# RC_Remote_SCH.net
KiCad netlist of a schematic drawn in Altium Designer
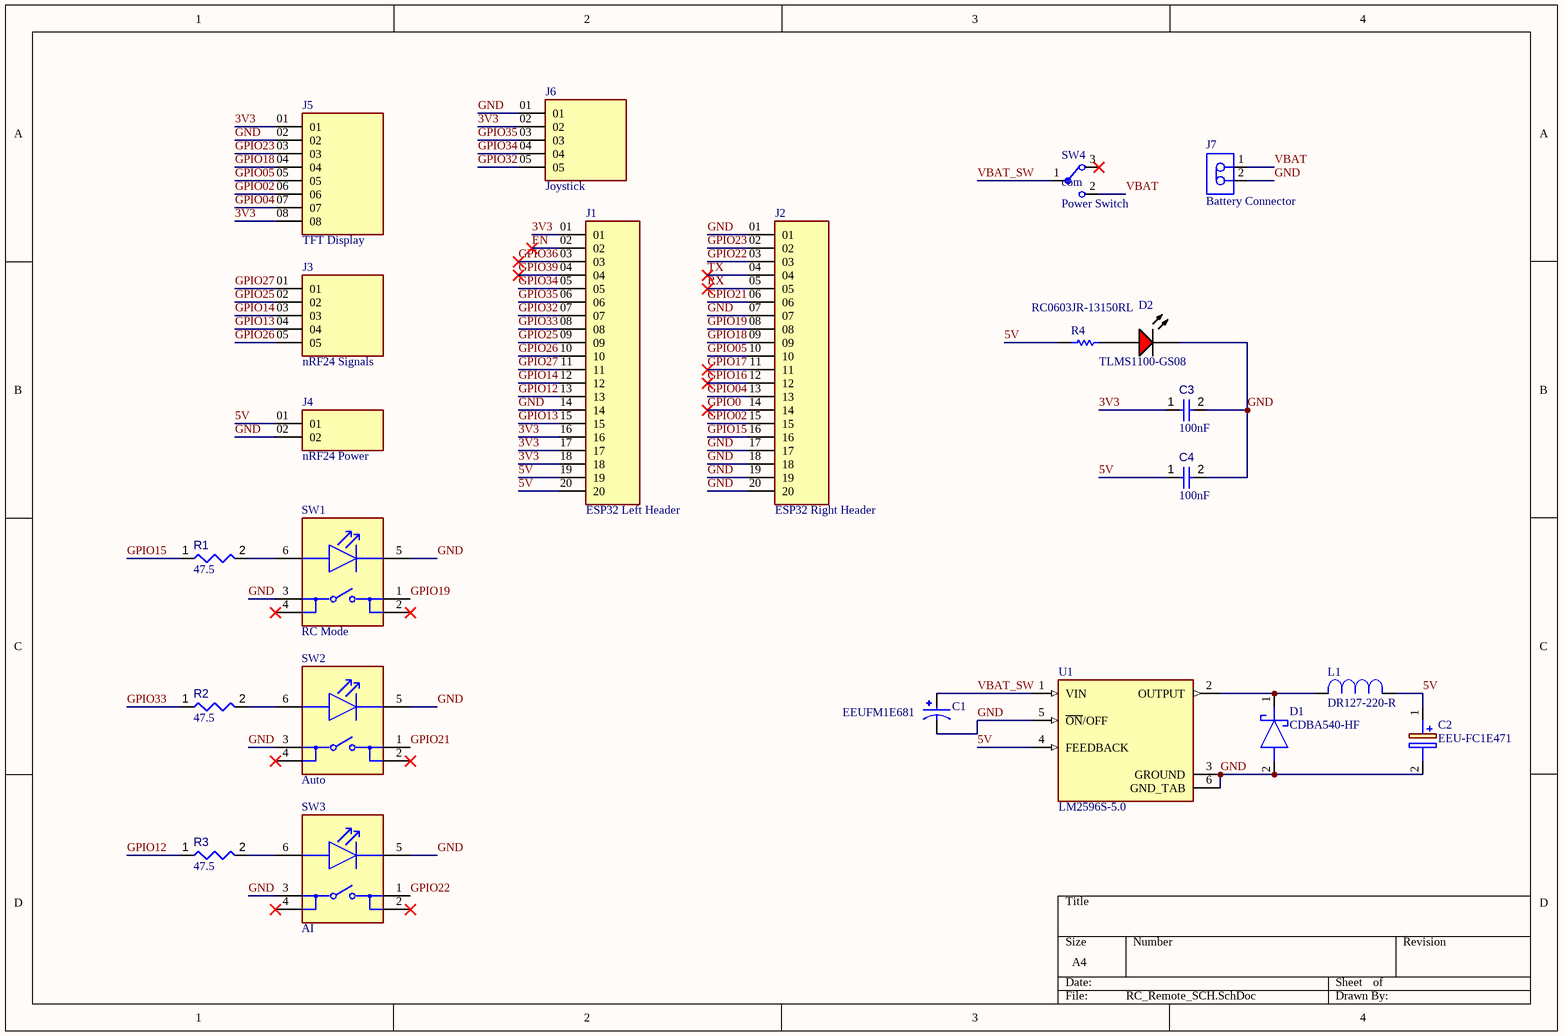
[diagram p0: RC_Remote_SCH.SchDoc]

(export (version "E")
  (design (tool "Eeschema 10.0.6"))
  (components
    (comp (ref "C1")
      (value "EEUFM1E681")
      (footprint "CAPPRD500W60D1000H2000")
      (description "680F 25V Aluminum Electrolytic Capacitors Radial, Can 5000 Hrs @ 105C")
      (fields (field (name "MF") "Panasonic") (field (name "DIGI-KEY_PART_NUMBER") "P12390-ND"))
      (libsource (lib "EEUFM1E681") (part "EEUFM1E681"))
    )
    (comp (ref "C2")
      (value "EEU-FC1E471")
      (footprint "SamacSys:CAPPRD350W65D815H2200")
      (description "Capacitor Polarised")
      (fields (field (name "MOUSER PART NUMBER") "667-EEU-FC1E471"))
      (libsource (lib "*") (part "EEU-FC1E471"))
    )
    (comp (ref "C3")
      (value "100nF")
      (footprint "CAPC1608X90X40NL10T20")
      (description "Chip Capacitor, 100 nF, +/- 10%, 50 V, 0603 (1608 Metric)")
      (fields (field (name "TOLERANCE") "10%") (field (name "Comment") "Capacitor 100 nF +/-10% 50 V 0603"))
      (libsource (lib "Shubh Patel") (part "CAP-NP-2"))
    )
    (comp (ref "C4")
      (value "100nF")
      (footprint "CAPC1608X90X40NL10T20")
      (description "Chip Capacitor, 100 nF, +/- 10%, 50 V, 0603 (1608 Metric)")
      (fields (field (name "TOLERANCE") "10%") (field (name "Comment") "Capacitor 100 nF +/-10% 50 V 0603"))
      (libsource (lib "Shubh Patel") (part "CAP-NP-2"))
    )
    (comp (ref "D1")
      (value "CDBA540-HF")
      (footprint "SamacSys:DIOM5225X250N")
      (description "Schottky Diode")
      (fields (field (name "MOUSER PART NUMBER") "750-CDBA540-HF"))
      (libsource (lib "*") (part "CDBA540-HF"))
    )
    (comp (ref "D2")
      (value "TLMS1100-GS08")
      (footprint "VISH-TLMX1100_V")
      (description "Red Led, 20mA, 2.1 V, -40 to 100 degC, 2-Pin SMD (0603), RoHS, Tape and Reel")
      (fields (field (name "MANUFACTURER") "Vishay Semiconductor") (field (name "POWER") "90mW"))
      (libsource (lib "Shubh Patel") (part "LED-RED-AK-2"))
    )
    (comp (ref "J1")
      (value "ESP32 Left Header")
      (footprint "SAMTEC_SSQ-120-XX-X-S")
      (description "20 Position Receptacle Connector 0.100 (2.54mm) Through Hole Gold")
      (fields (field (name "MF") "Samtec") (field (name "MP") "SSQ-120-22-F-S"))
      (libsource (lib "SSQ-120-XX-X-S") (part "SSQ-120-XX-X-S"))
    )
    (comp (ref "J2")
      (value "ESP32 Right Header")
      (footprint "SAMTEC_SSQ-120-XX-X-S")
      (description "20 Position Receptacle Connector 0.100 (2.54mm) Through Hole Gold")
      (fields (field (name "MF") "Samtec") (field (name "MP") "SSQ-120-22-F-S"))
      (libsource (lib "SSQ-120-XX-X-S") (part "SSQ-120-XX-X-S"))
    )
    (comp (ref "J3")
      (value "nRF24 Signals")
      (footprint "SAMTEC_SSQ-105-02-T-S")
      (description "Headers & Wire Housings .100 Tiger Buy Socket Strip, Square Tail")
      (fields (field (name "MF") "Samtec") (field (name "MP") "SSQ-105-02-T-S"))
      (libsource (lib "SSQ-105-02-T-S") (part "SSQ-105-02-T-S"))
    )
    (comp (ref "J4")
      (value "nRF24 Power")
      (footprint "SAMTEC_SSQ-102-02-T-S")
      (description "SSQ Series .100 Tiger Buyâ„¢ Socket Strip, Square Tail")
      (fields (field (name "MF") "Samtec Inc.") (field (name "MP") "SSQ-102-02-T-S"))
      (libsource (lib "SSQ-102-02-T-S") (part "SSQ-102-02-T-S"))
    )
    (comp (ref "J5")
      (value "TFT Display")
      (footprint "SAMTEC_SSQ-108-02-T-S")
      (description "Headers & Wire Housings .100 Tiger Buy Socket Strip, Square Tail")
      (fields (field (name "MF") "Samtec") (field (name "MP") "SSQ-108-02-T-S"))
      (libsource (lib "SSQ-108-02-T-S") (part "SSQ-108-02-T-S"))
    )
    (comp (ref "J6")
      (value "Joystick")
      (footprint "SAMTEC_SSQ-105-02-T-S")
      (description "Headers & Wire Housings .100 Tiger Buy Socket Strip, Square Tail")
      (fields (field (name "MF") "Samtec") (field (name "MP") "SSQ-105-02-T-S"))
      (libsource (lib "SSQ-105-02-T-S") (part "SSQ-105-02-T-S"))
    )
    (comp (ref "J7")
      (value "Battery Connector")
      (footprint "JST-B2B-PH-K-S_V")
      (fields (field (name "MANUFACTURER") "JST"))
      (libsource (lib "Altium Content Vault") (part "CN-2P-F-QF2"))
    )
    (comp (ref "L1")
      (value "DR127-220-R")
      (footprint "INDM125125X800N")
      (description "22ÂµH Shielded Wirewound Inductor 4A 39.1mOhm Nonstandard")
      (fields (field (name "MF") "Eaton") (field (name "DIGI-KEY_PART_NUMBER") "513-1044-1-ND"))
      (libsource (lib "DR127-220-R") (part "DR127-220-R"))
    )
    (comp (ref "R1")
      (value "47.5")
      (footprint "RESA60-630X240")
      (description "Axial Resistor, 47.5 Ohm, +/- 1%, 0.25 W, -55 to 155 degC, 2-Pin THD, RoHS, Bulk")
      (fields (field (name "MANUFACTURER") "Yageo") (field (name "TOLERANCE") "1%"))
      (libsource (lib "Shubh Patel") (part "RES-2"))
    )
    (comp (ref "R2")
      (value "47.5")
      (footprint "RESA60-630X240")
      (description "Axial Resistor, 47.5 Ohm, +/- 1%, 0.25 W, -55 to 155 degC, 2-Pin THD, RoHS, Bulk")
      (fields (field (name "MANUFACTURER") "Yageo") (field (name "TOLERANCE") "1%"))
      (libsource (lib "Shubh Patel") (part "RES-2"))
    )
    (comp (ref "R3")
      (value "47.5")
      (footprint "RESA60-630X240")
      (description "Axial Resistor, 47.5 Ohm, +/- 1%, 0.25 W, -55 to 155 degC, 2-Pin THD, RoHS, Bulk")
      (fields (field (name "MANUFACTURER") "Yageo") (field (name "TOLERANCE") "1%"))
      (libsource (lib "Shubh Patel") (part "RES-2"))
    )
    (comp (ref "R4")
      (value "RC0603JR-13150RL")
      (footprint "RESC1608X55X25ML10T15")
      (fields (field (name "MANUFACTURER") "Yageo"))
      (libsource (lib "Altium Content Vault") (part "RES"))
    )
    (comp (ref "SW1")
      (value "RC Mode")
      (footprint "FP-B3W-9002-Y1N-MFG")
      (description "SWITCH TACTILE SPST-NO 0.05A 24V")
      (libsource (lib "Altium Content Vault") (part "22b904902572c3c727f825aa1c29889"))
    )
    (comp (ref "SW2")
      (value "Auto")
      (footprint "FP-B3W-9002-Y1N-MFG")
      (description "SWITCH TACTILE SPST-NO 0.05A 24V")
      (libsource (lib "Altium Content Vault") (part "22b904902572c3c727f825aa1c29889"))
    )
    (comp (ref "SW3")
      (value "AI")
      (footprint "FP-B3W-9002-Y1N-MFG")
      (description "SWITCH TACTILE SPST-NO 0.05A 24V")
      (libsource (lib "Altium Content Vault") (part "22b904902572c3c727f825aa1c29889"))
    )
    (comp (ref "SW4")
      (value "Power Switch")
      (footprint "450301014042")
      (fields
        (field (name "MF") "{'manufacturer': u'~{W}xfcrth Elektronik'}")
        (field (name "MP") "450301014042")
      )
      (libsource (lib "450301014042") (part "450301014042"))
    )
    (comp (ref "U1")
      (value "LM2596S-5.0")
      (footprint "TO170P1524X483-6N")
      (description "SIMPLE SWITCHERÂ® 4.5V to 40V, 3A Low Component Count Step-Down Regulator")
      (fields (field (name "MF") "Texas Instruments") (field (name "MP") "LM2596S-5.0/NOPB"))
      (libsource (lib "LM2596S-5.0") (part "LM2596S-5.0"))
    )
  )
  (nets
    (net (code "1") (name "/3V3") (class "Default")
      (node (ref "C3") (pin "1") (pinfunction "1_1") (pintype "passive"))
      (node (ref "J1") (pin "01") (pinfunction "01_01") (pintype "passive"))
      (node (ref "J1") (pin "16") (pinfunction "16_16") (pintype "passive"))
      (node (ref "J1") (pin "17") (pinfunction "17_17") (pintype "passive"))
      (node (ref "J1") (pin "18") (pinfunction "18_18") (pintype "passive"))
      (node (ref "J5") (pin "01") (pinfunction "01_01") (pintype "passive"))
      (node (ref "J5") (pin "08") (pinfunction "08_08") (pintype "passive"))
      (node (ref "J6") (pin "02") (pinfunction "02_02") (pintype "passive"))
    )
    (net (code "2") (name "/5V") (class "Default")
      (node (ref "C2") (pin "1") (pinfunction "+_1") (pintype "passive"))
      (node (ref "C4") (pin "1") (pinfunction "1_1") (pintype "passive"))
      (node (ref "J1") (pin "19") (pinfunction "19_19") (pintype "passive"))
      (node (ref "J1") (pin "20") (pinfunction "20_20") (pintype "passive"))
      (node (ref "J4") (pin "01") (pinfunction "01_01") (pintype "passive"))
      (node (ref "L1") (pin "1") (pinfunction "1_1") (pintype "passive"))
      (node (ref "R4") (pin "1") (pinfunction "1_1") (pintype "passive"))
      (node (ref "U1") (pin "4") (pinfunction "FEEDBACK_4") (pintype "input"))
    )
    (net (code "3") (name "/EN") (class "Default")
      (node (ref "J1") (pin "02") (pinfunction "02_02") (pintype "passive+no_connect"))
    )
    (net (code "4") (name "/GND") (class "Default")
      (node (ref "C1") (pin "N") (pinfunction "N_N") (pintype "passive"))
      (node (ref "C2") (pin "2") (pinfunction "-_2") (pintype "passive"))
      (node (ref "C3") (pin "2") (pinfunction "2_2") (pintype "passive"))
      (node (ref "C4") (pin "2") (pinfunction "2_2") (pintype "passive"))
      (node (ref "D1") (pin "2") (pinfunction "A_2") (pintype "passive"))
      (node (ref "D2") (pin "2") (pinfunction "K_2") (pintype "passive"))
      (node (ref "J1") (pin "14") (pinfunction "14_14") (pintype "passive"))
      (node (ref "J2") (pin "01") (pinfunction "01_01") (pintype "passive"))
      (node (ref "J2") (pin "07") (pinfunction "07_07") (pintype "passive"))
      (node (ref "J2") (pin "17") (pinfunction "17_17") (pintype "passive"))
      (node (ref "J2") (pin "18") (pinfunction "18_18") (pintype "passive"))
      (node (ref "J2") (pin "19") (pinfunction "19_19") (pintype "passive"))
      (node (ref "J2") (pin "20") (pinfunction "20_20") (pintype "passive"))
      (node (ref "J4") (pin "02") (pinfunction "02_02") (pintype "passive"))
      (node (ref "J5") (pin "02") (pinfunction "02_02") (pintype "passive"))
      (node (ref "J6") (pin "01") (pinfunction "01_01") (pintype "passive"))
      (node (ref "J7") (pin "2") (pinfunction "2_2") (pintype "passive"))
      (node (ref "SW1") (pin "3") (pinfunction "3_3") (pintype "passive"))
      (node (ref "SW1") (pin "5") (pinfunction "C_5") (pintype "passive"))
      (node (ref "SW2") (pin "3") (pinfunction "3_3") (pintype "passive"))
      (node (ref "SW2") (pin "5") (pinfunction "C_5") (pintype "passive"))
      (node (ref "SW3") (pin "3") (pinfunction "3_3") (pintype "passive"))
      (node (ref "SW3") (pin "5") (pinfunction "C_5") (pintype "passive"))
      (node (ref "U1") (pin "3") (pinfunction "GROUND_3") (pintype "power_in"))
      (node (ref "U1") (pin "5") (pinfunction "~{ON}/OFF_5") (pintype "input"))
      (node (ref "U1") (pin "6") (pinfunction "GND_TAB_6") (pintype "power_in"))
    )
    (net (code "5") (name "/GPIO0") (class "Default")
      (node (ref "J2") (pin "14") (pinfunction "14_14") (pintype "passive+no_connect"))
    )
    (net (code "6") (name "/GPIO02") (class "Default")
      (node (ref "J2") (pin "15") (pinfunction "15_15") (pintype "passive"))
      (node (ref "J5") (pin "06") (pinfunction "06_06") (pintype "passive"))
    )
    (net (code "7") (name "/GPIO04") (class "Default")
      (node (ref "J2") (pin "13") (pinfunction "13_13") (pintype "passive"))
      (node (ref "J5") (pin "07") (pinfunction "07_07") (pintype "passive"))
    )
    (net (code "8") (name "/GPIO05") (class "Default")
      (node (ref "J2") (pin "10") (pinfunction "10_10") (pintype "passive"))
      (node (ref "J5") (pin "05") (pinfunction "05_05") (pintype "passive"))
    )
    (net (code "9") (name "/GPIO12") (class "Default")
      (node (ref "J1") (pin "13") (pinfunction "13_13") (pintype "passive"))
      (node (ref "R3") (pin "1") (pinfunction "1_1") (pintype "passive"))
    )
    (net (code "10") (name "/GPIO13") (class "Default")
      (node (ref "J1") (pin "15") (pinfunction "15_15") (pintype "passive"))
      (node (ref "J3") (pin "04") (pinfunction "04_04") (pintype "passive"))
    )
    (net (code "11") (name "/GPIO14") (class "Default")
      (node (ref "J1") (pin "12") (pinfunction "12_12") (pintype "passive"))
      (node (ref "J3") (pin "03") (pinfunction "03_03") (pintype "passive"))
    )
    (net (code "12") (name "/GPIO15") (class "Default")
      (node (ref "J2") (pin "16") (pinfunction "16_16") (pintype "passive"))
      (node (ref "R1") (pin "1") (pinfunction "1_1") (pintype "passive"))
    )
    (net (code "13") (name "/GPIO16") (class "Default")
      (node (ref "J2") (pin "12") (pinfunction "12_12") (pintype "passive+no_connect"))
    )
    (net (code "14") (name "/GPIO17") (class "Default")
      (node (ref "J2") (pin "11") (pinfunction "11_11") (pintype "passive+no_connect"))
    )
    (net (code "15") (name "/GPIO18") (class "Default")
      (node (ref "J2") (pin "09") (pinfunction "09_09") (pintype "passive"))
      (node (ref "J5") (pin "04") (pinfunction "04_04") (pintype "passive"))
    )
    (net (code "16") (name "/GPIO19") (class "Default")
      (node (ref "J2") (pin "08") (pinfunction "08_08") (pintype "passive"))
      (node (ref "SW1") (pin "1") (pinfunction "1_1") (pintype "passive"))
    )
    (net (code "17") (name "/GPIO21") (class "Default")
      (node (ref "J2") (pin "06") (pinfunction "06_06") (pintype "passive"))
      (node (ref "SW2") (pin "1") (pinfunction "1_1") (pintype "passive"))
    )
    (net (code "18") (name "/GPIO22") (class "Default")
      (node (ref "J2") (pin "03") (pinfunction "03_03") (pintype "passive"))
      (node (ref "SW3") (pin "1") (pinfunction "1_1") (pintype "passive"))
    )
    (net (code "19") (name "/GPIO23") (class "Default")
      (node (ref "J2") (pin "02") (pinfunction "02_02") (pintype "passive"))
      (node (ref "J5") (pin "03") (pinfunction "03_03") (pintype "passive"))
    )
    (net (code "20") (name "/GPIO25") (class "Default")
      (node (ref "J1") (pin "09") (pinfunction "09_09") (pintype "passive"))
      (node (ref "J3") (pin "02") (pinfunction "02_02") (pintype "passive"))
    )
    (net (code "21") (name "/GPIO26") (class "Default")
      (node (ref "J1") (pin "10") (pinfunction "10_10") (pintype "passive"))
      (node (ref "J3") (pin "05") (pinfunction "05_05") (pintype "passive"))
    )
    (net (code "22") (name "/GPIO27") (class "Default")
      (node (ref "J1") (pin "11") (pinfunction "11_11") (pintype "passive"))
      (node (ref "J3") (pin "01") (pinfunction "01_01") (pintype "passive"))
    )
    (net (code "23") (name "/GPIO32") (class "Default")
      (node (ref "J1") (pin "07") (pinfunction "07_07") (pintype "passive"))
      (node (ref "J6") (pin "05") (pinfunction "05_05") (pintype "passive"))
    )
    (net (code "24") (name "/GPIO33") (class "Default")
      (node (ref "J1") (pin "08") (pinfunction "08_08") (pintype "passive"))
      (node (ref "R2") (pin "1") (pinfunction "1_1") (pintype "passive"))
    )
    (net (code "25") (name "/GPIO34") (class "Default")
      (node (ref "J1") (pin "05") (pinfunction "05_05") (pintype "passive"))
      (node (ref "J6") (pin "04") (pinfunction "04_04") (pintype "passive"))
    )
    (net (code "26") (name "/GPIO35") (class "Default")
      (node (ref "J1") (pin "06") (pinfunction "06_06") (pintype "passive"))
      (node (ref "J6") (pin "03") (pinfunction "03_03") (pintype "passive"))
    )
    (net (code "27") (name "/GPIO36") (class "Default")
      (node (ref "J1") (pin "03") (pinfunction "03_03") (pintype "passive+no_connect"))
    )
    (net (code "28") (name "/GPIO39") (class "Default")
      (node (ref "J1") (pin "04") (pinfunction "04_04") (pintype "passive+no_connect"))
    )
    (net (code "29") (name "/RX") (class "Default")
      (node (ref "J2") (pin "05") (pinfunction "05_05") (pintype "passive+no_connect"))
    )
    (net (code "30") (name "/TX") (class "Default")
      (node (ref "J2") (pin "04") (pinfunction "04_04") (pintype "passive+no_connect"))
    )
    (net (code "31") (name "/VBAT") (class "Default")
      (node (ref "J7") (pin "1") (pinfunction "1_1") (pintype "passive"))
      (node (ref "SW4") (pin "2") (pinfunction "2_2") (pintype "passive"))
    )
    (net (code "32") (name "/VBAT_SW") (class "Default")
      (node (ref "C1") (pin "P") (pinfunction "P_P") (pintype "passive"))
      (node (ref "SW4") (pin "1") (pinfunction "1_1") (pintype "passive"))
      (node (ref "U1") (pin "1") (pinfunction "VIN_1") (pintype "input"))
    )
    (net (code "33") (name "Net-(D1-K)") (class "Default")
      (node (ref "D1") (pin "1") (pinfunction "K_1") (pintype "passive"))
      (node (ref "L1") (pin "2") (pinfunction "2_2") (pintype "passive"))
      (node (ref "U1") (pin "2") (pinfunction "OUTPUT_2") (pintype "output"))
    )
    (net (code "34") (name "Net-(D2-A)") (class "Default")
      (node (ref "D2") (pin "1") (pinfunction "A_1") (pintype "passive"))
      (node (ref "R4") (pin "2") (pinfunction "2_2") (pintype "passive"))
    )
    (net (code "35") (name "Net-(SW1-A)") (class "Default")
      (node (ref "R1") (pin "2") (pinfunction "2_2") (pintype "passive"))
      (node (ref "SW1") (pin "6") (pinfunction "A_6") (pintype "passive"))
    )
    (net (code "36") (name "Net-(SW2-A)") (class "Default")
      (node (ref "R2") (pin "2") (pinfunction "2_2") (pintype "passive"))
      (node (ref "SW2") (pin "6") (pinfunction "A_6") (pintype "passive"))
    )
    (net (code "37") (name "Net-(SW3-A)") (class "Default")
      (node (ref "R3") (pin "2") (pinfunction "2_2") (pintype "passive"))
      (node (ref "SW3") (pin "6") (pinfunction "A_6") (pintype "passive"))
    )
    (net (code "38") (name "unconnected-(SW1-Pad2)") (class "Default")
      (node (ref "SW1") (pin "2") (pinfunction "2_2") (pintype "passive+no_connect"))
    )
    (net (code "39") (name "unconnected-(SW1-Pad4)") (class "Default")
      (node (ref "SW1") (pin "4") (pinfunction "4_4") (pintype "passive+no_connect"))
    )
    (net (code "40") (name "unconnected-(SW2-Pad2)") (class "Default")
      (node (ref "SW2") (pin "2") (pinfunction "2_2") (pintype "passive+no_connect"))
    )
    (net (code "41") (name "unconnected-(SW2-Pad4)") (class "Default")
      (node (ref "SW2") (pin "4") (pinfunction "4_4") (pintype "passive+no_connect"))
    )
    (net (code "42") (name "unconnected-(SW3-Pad2)") (class "Default")
      (node (ref "SW3") (pin "2") (pinfunction "2_2") (pintype "passive+no_connect"))
    )
    (net (code "43") (name "unconnected-(SW3-Pad4)") (class "Default")
      (node (ref "SW3") (pin "4") (pinfunction "4_4") (pintype "passive+no_connect"))
    )
    (net (code "44") (name "unconnected-(SW4-Pad3)") (class "Default")
      (node (ref "SW4") (pin "3") (pinfunction "3_3") (pintype "passive+no_connect"))
    )
  )
)
